# FMC_HPC_UFL_DEBUG_J1_J84.net
KiCad netlist of a schematic drawn in Altium Designer
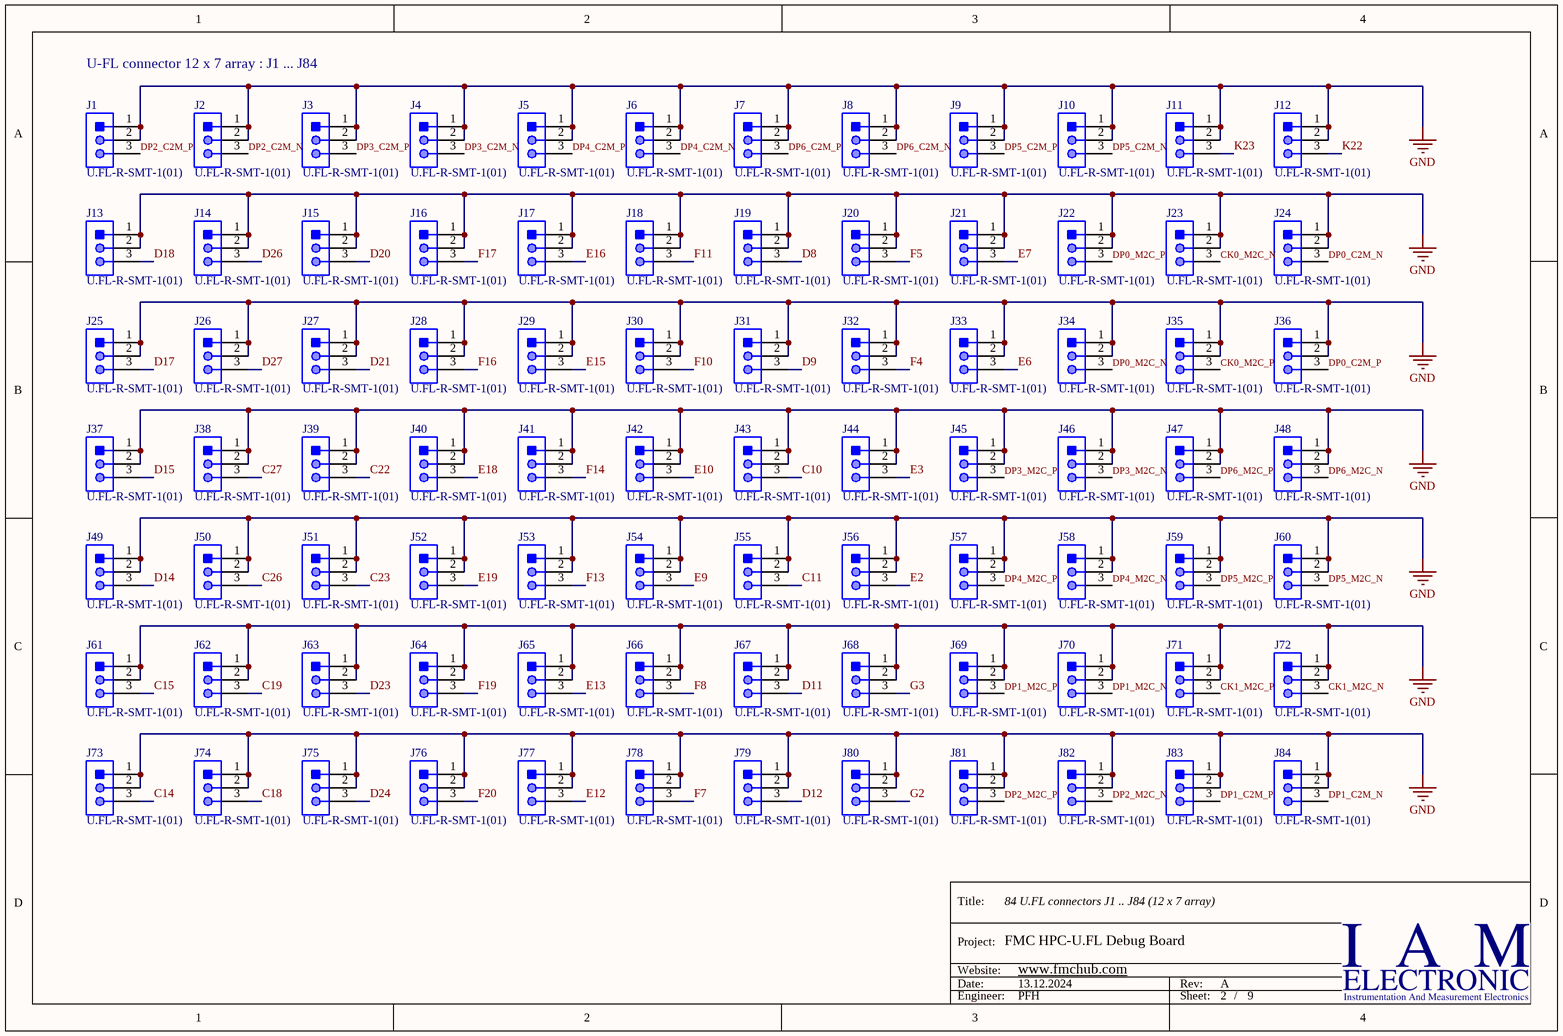
[diagram p0: FMC_HPC_UFL_DEBUG_J1_J84.SchDoc]

(export (version "E")
  (design (tool "Eeschema 10.0.6"))
  (components
    (comp (ref "J1")
      (value "U.FL-R-SMT-1(01)")
      (footprint "HRS-U.FL-R-SMT-3_V")
      (description "Ultra Small Coaxial Connector, 6 GHz, -40 to 90 degC, 3-Pin SMD, RoHS, Bulk")
      (fields (field (name "MANUFACTURER") "Hirose Electric"))
      (libsource (lib "Altium Content Vault") (part "CN-1P-M-R3"))
    )
    (comp (ref "J2")
      (value "U.FL-R-SMT-1(01)")
      (footprint "HRS-U.FL-R-SMT-3_V")
      (description "Ultra Small Coaxial Connector, 6 GHz, -40 to 90 degC, 3-Pin SMD, RoHS, Bulk")
      (fields (field (name "MANUFACTURER") "Hirose Electric"))
      (libsource (lib "Altium Content Vault") (part "CN-1P-M-R3"))
    )
    (comp (ref "J3")
      (value "U.FL-R-SMT-1(01)")
      (footprint "HRS-U.FL-R-SMT-3_V")
      (description "Ultra Small Coaxial Connector, 6 GHz, -40 to 90 degC, 3-Pin SMD, RoHS, Bulk")
      (fields (field (name "MANUFACTURER") "Hirose Electric"))
      (libsource (lib "Altium Content Vault") (part "CN-1P-M-R3"))
    )
    (comp (ref "J4")
      (value "U.FL-R-SMT-1(01)")
      (footprint "HRS-U.FL-R-SMT-3_V")
      (description "Ultra Small Coaxial Connector, 6 GHz, -40 to 90 degC, 3-Pin SMD, RoHS, Bulk")
      (fields (field (name "MANUFACTURER") "Hirose Electric"))
      (libsource (lib "Altium Content Vault") (part "CN-1P-M-R3"))
    )
    (comp (ref "J5")
      (value "U.FL-R-SMT-1(01)")
      (footprint "HRS-U.FL-R-SMT-3_V")
      (description "Ultra Small Coaxial Connector, 6 GHz, -40 to 90 degC, 3-Pin SMD, RoHS, Bulk")
      (fields (field (name "MANUFACTURER") "Hirose Electric"))
      (libsource (lib "Altium Content Vault") (part "CN-1P-M-R3"))
    )
    (comp (ref "J6")
      (value "U.FL-R-SMT-1(01)")
      (footprint "HRS-U.FL-R-SMT-3_V")
      (description "Ultra Small Coaxial Connector, 6 GHz, -40 to 90 degC, 3-Pin SMD, RoHS, Bulk")
      (fields (field (name "MANUFACTURER") "Hirose Electric"))
      (libsource (lib "Altium Content Vault") (part "CN-1P-M-R3"))
    )
    (comp (ref "J7")
      (value "U.FL-R-SMT-1(01)")
      (footprint "HRS-U.FL-R-SMT-3_V")
      (description "Ultra Small Coaxial Connector, 6 GHz, -40 to 90 degC, 3-Pin SMD, RoHS, Bulk")
      (fields (field (name "MANUFACTURER") "Hirose Electric"))
      (libsource (lib "Altium Content Vault") (part "CN-1P-M-R3"))
    )
    (comp (ref "J8")
      (value "U.FL-R-SMT-1(01)")
      (footprint "HRS-U.FL-R-SMT-3_V")
      (description "Ultra Small Coaxial Connector, 6 GHz, -40 to 90 degC, 3-Pin SMD, RoHS, Bulk")
      (fields (field (name "MANUFACTURER") "Hirose Electric"))
      (libsource (lib "Altium Content Vault") (part "CN-1P-M-R3"))
    )
    (comp (ref "J9")
      (value "U.FL-R-SMT-1(01)")
      (footprint "HRS-U.FL-R-SMT-3_V")
      (description "Ultra Small Coaxial Connector, 6 GHz, -40 to 90 degC, 3-Pin SMD, RoHS, Bulk")
      (fields (field (name "MANUFACTURER") "Hirose Electric"))
      (libsource (lib "Altium Content Vault") (part "CN-1P-M-R3"))
    )
    (comp (ref "J10")
      (value "U.FL-R-SMT-1(01)")
      (footprint "HRS-U.FL-R-SMT-3_V")
      (description "Ultra Small Coaxial Connector, 6 GHz, -40 to 90 degC, 3-Pin SMD, RoHS, Bulk")
      (fields (field (name "MANUFACTURER") "Hirose Electric"))
      (libsource (lib "Altium Content Vault") (part "CN-1P-M-R3"))
    )
    (comp (ref "J11")
      (value "U.FL-R-SMT-1(01)")
      (footprint "HRS-U.FL-R-SMT-3_V")
      (description "Ultra Small Coaxial Connector, 6 GHz, -40 to 90 degC, 3-Pin SMD, RoHS, Bulk")
      (fields (field (name "MANUFACTURER") "Hirose Electric"))
      (libsource (lib "Altium Content Vault") (part "CN-1P-M-R3"))
    )
    (comp (ref "J12")
      (value "U.FL-R-SMT-1(01)")
      (footprint "HRS-U.FL-R-SMT-3_V")
      (description "Ultra Small Coaxial Connector, 6 GHz, -40 to 90 degC, 3-Pin SMD, RoHS, Bulk")
      (fields (field (name "MANUFACTURER") "Hirose Electric"))
      (libsource (lib "Altium Content Vault") (part "CN-1P-M-R3"))
    )
    (comp (ref "J13")
      (value "U.FL-R-SMT-1(01)")
      (footprint "HRS-U.FL-R-SMT-3_V")
      (description "Ultra Small Coaxial Connector, 6 GHz, -40 to 90 degC, 3-Pin SMD, RoHS, Bulk")
      (fields (field (name "MANUFACTURER") "Hirose Electric"))
      (libsource (lib "Altium Content Vault") (part "CN-1P-M-R3"))
    )
    (comp (ref "J14")
      (value "U.FL-R-SMT-1(01)")
      (footprint "HRS-U.FL-R-SMT-3_V")
      (description "Ultra Small Coaxial Connector, 6 GHz, -40 to 90 degC, 3-Pin SMD, RoHS, Bulk")
      (fields (field (name "MANUFACTURER") "Hirose Electric"))
      (libsource (lib "Altium Content Vault") (part "CN-1P-M-R3"))
    )
    (comp (ref "J15")
      (value "U.FL-R-SMT-1(01)")
      (footprint "HRS-U.FL-R-SMT-3_V")
      (description "Ultra Small Coaxial Connector, 6 GHz, -40 to 90 degC, 3-Pin SMD, RoHS, Bulk")
      (fields (field (name "MANUFACTURER") "Hirose Electric"))
      (libsource (lib "Altium Content Vault") (part "CN-1P-M-R3"))
    )
    (comp (ref "J16")
      (value "U.FL-R-SMT-1(01)")
      (footprint "HRS-U.FL-R-SMT-3_V")
      (description "Ultra Small Coaxial Connector, 6 GHz, -40 to 90 degC, 3-Pin SMD, RoHS, Bulk")
      (fields (field (name "MANUFACTURER") "Hirose Electric"))
      (libsource (lib "Altium Content Vault") (part "CN-1P-M-R3"))
    )
    (comp (ref "J17")
      (value "U.FL-R-SMT-1(01)")
      (footprint "HRS-U.FL-R-SMT-3_V")
      (description "Ultra Small Coaxial Connector, 6 GHz, -40 to 90 degC, 3-Pin SMD, RoHS, Bulk")
      (fields (field (name "MANUFACTURER") "Hirose Electric"))
      (libsource (lib "Altium Content Vault") (part "CN-1P-M-R3"))
    )
    (comp (ref "J18")
      (value "U.FL-R-SMT-1(01)")
      (footprint "HRS-U.FL-R-SMT-3_V")
      (description "Ultra Small Coaxial Connector, 6 GHz, -40 to 90 degC, 3-Pin SMD, RoHS, Bulk")
      (fields (field (name "MANUFACTURER") "Hirose Electric"))
      (libsource (lib "Altium Content Vault") (part "CN-1P-M-R3"))
    )
    (comp (ref "J19")
      (value "U.FL-R-SMT-1(01)")
      (footprint "HRS-U.FL-R-SMT-3_V")
      (description "Ultra Small Coaxial Connector, 6 GHz, -40 to 90 degC, 3-Pin SMD, RoHS, Bulk")
      (fields (field (name "MANUFACTURER") "Hirose Electric"))
      (libsource (lib "Altium Content Vault") (part "CN-1P-M-R3"))
    )
    (comp (ref "J20")
      (value "U.FL-R-SMT-1(01)")
      (footprint "HRS-U.FL-R-SMT-3_V")
      (description "Ultra Small Coaxial Connector, 6 GHz, -40 to 90 degC, 3-Pin SMD, RoHS, Bulk")
      (fields (field (name "MANUFACTURER") "Hirose Electric"))
      (libsource (lib "Altium Content Vault") (part "CN-1P-M-R3"))
    )
    (comp (ref "J21")
      (value "U.FL-R-SMT-1(01)")
      (footprint "HRS-U.FL-R-SMT-3_V")
      (description "Ultra Small Coaxial Connector, 6 GHz, -40 to 90 degC, 3-Pin SMD, RoHS, Bulk")
      (fields (field (name "MANUFACTURER") "Hirose Electric"))
      (libsource (lib "Altium Content Vault") (part "CN-1P-M-R3"))
    )
    (comp (ref "J22")
      (value "U.FL-R-SMT-1(01)")
      (footprint "HRS-U.FL-R-SMT-3_V")
      (description "Ultra Small Coaxial Connector, 6 GHz, -40 to 90 degC, 3-Pin SMD, RoHS, Bulk")
      (fields (field (name "MANUFACTURER") "Hirose Electric"))
      (libsource (lib "Altium Content Vault") (part "CN-1P-M-R3"))
    )
    (comp (ref "J23")
      (value "U.FL-R-SMT-1(01)")
      (footprint "HRS-U.FL-R-SMT-3_V")
      (description "Ultra Small Coaxial Connector, 6 GHz, -40 to 90 degC, 3-Pin SMD, RoHS, Bulk")
      (fields (field (name "MANUFACTURER") "Hirose Electric"))
      (libsource (lib "Altium Content Vault") (part "CN-1P-M-R3"))
    )
    (comp (ref "J24")
      (value "U.FL-R-SMT-1(01)")
      (footprint "HRS-U.FL-R-SMT-3_V")
      (description "Ultra Small Coaxial Connector, 6 GHz, -40 to 90 degC, 3-Pin SMD, RoHS, Bulk")
      (fields (field (name "MANUFACTURER") "Hirose Electric"))
      (libsource (lib "Altium Content Vault") (part "CN-1P-M-R3"))
    )
    (comp (ref "J25")
      (value "U.FL-R-SMT-1(01)")
      (footprint "HRS-U.FL-R-SMT-3_V")
      (description "Ultra Small Coaxial Connector, 6 GHz, -40 to 90 degC, 3-Pin SMD, RoHS, Bulk")
      (fields (field (name "MANUFACTURER") "Hirose Electric"))
      (libsource (lib "Altium Content Vault") (part "CN-1P-M-R3"))
    )
    (comp (ref "J26")
      (value "U.FL-R-SMT-1(01)")
      (footprint "HRS-U.FL-R-SMT-3_V")
      (description "Ultra Small Coaxial Connector, 6 GHz, -40 to 90 degC, 3-Pin SMD, RoHS, Bulk")
      (fields (field (name "MANUFACTURER") "Hirose Electric"))
      (libsource (lib "Altium Content Vault") (part "CN-1P-M-R3"))
    )
    (comp (ref "J27")
      (value "U.FL-R-SMT-1(01)")
      (footprint "HRS-U.FL-R-SMT-3_V")
      (description "Ultra Small Coaxial Connector, 6 GHz, -40 to 90 degC, 3-Pin SMD, RoHS, Bulk")
      (fields (field (name "MANUFACTURER") "Hirose Electric"))
      (libsource (lib "Altium Content Vault") (part "CN-1P-M-R3"))
    )
    (comp (ref "J28")
      (value "U.FL-R-SMT-1(01)")
      (footprint "HRS-U.FL-R-SMT-3_V")
      (description "Ultra Small Coaxial Connector, 6 GHz, -40 to 90 degC, 3-Pin SMD, RoHS, Bulk")
      (fields (field (name "MANUFACTURER") "Hirose Electric"))
      (libsource (lib "Altium Content Vault") (part "CN-1P-M-R3"))
    )
    (comp (ref "J29")
      (value "U.FL-R-SMT-1(01)")
      (footprint "HRS-U.FL-R-SMT-3_V")
      (description "Ultra Small Coaxial Connector, 6 GHz, -40 to 90 degC, 3-Pin SMD, RoHS, Bulk")
      (fields (field (name "MANUFACTURER") "Hirose Electric"))
      (libsource (lib "Altium Content Vault") (part "CN-1P-M-R3"))
    )
    (comp (ref "J30")
      (value "U.FL-R-SMT-1(01)")
      (footprint "HRS-U.FL-R-SMT-3_V")
      (description "Ultra Small Coaxial Connector, 6 GHz, -40 to 90 degC, 3-Pin SMD, RoHS, Bulk")
      (fields (field (name "MANUFACTURER") "Hirose Electric"))
      (libsource (lib "Altium Content Vault") (part "CN-1P-M-R3"))
    )
    (comp (ref "J31")
      (value "U.FL-R-SMT-1(01)")
      (footprint "HRS-U.FL-R-SMT-3_V")
      (description "Ultra Small Coaxial Connector, 6 GHz, -40 to 90 degC, 3-Pin SMD, RoHS, Bulk")
      (fields (field (name "MANUFACTURER") "Hirose Electric"))
      (libsource (lib "Altium Content Vault") (part "CN-1P-M-R3"))
    )
    (comp (ref "J32")
      (value "U.FL-R-SMT-1(01)")
      (footprint "HRS-U.FL-R-SMT-3_V")
      (description "Ultra Small Coaxial Connector, 6 GHz, -40 to 90 degC, 3-Pin SMD, RoHS, Bulk")
      (fields (field (name "MANUFACTURER") "Hirose Electric"))
      (libsource (lib "Altium Content Vault") (part "CN-1P-M-R3"))
    )
    (comp (ref "J33")
      (value "U.FL-R-SMT-1(01)")
      (footprint "HRS-U.FL-R-SMT-3_V")
      (description "Ultra Small Coaxial Connector, 6 GHz, -40 to 90 degC, 3-Pin SMD, RoHS, Bulk")
      (fields (field (name "MANUFACTURER") "Hirose Electric"))
      (libsource (lib "Altium Content Vault") (part "CN-1P-M-R3"))
    )
    (comp (ref "J34")
      (value "U.FL-R-SMT-1(01)")
      (footprint "HRS-U.FL-R-SMT-3_V")
      (description "Ultra Small Coaxial Connector, 6 GHz, -40 to 90 degC, 3-Pin SMD, RoHS, Bulk")
      (fields (field (name "MANUFACTURER") "Hirose Electric"))
      (libsource (lib "Altium Content Vault") (part "CN-1P-M-R3"))
    )
    (comp (ref "J35")
      (value "U.FL-R-SMT-1(01)")
      (footprint "HRS-U.FL-R-SMT-3_V")
      (description "Ultra Small Coaxial Connector, 6 GHz, -40 to 90 degC, 3-Pin SMD, RoHS, Bulk")
      (fields (field (name "MANUFACTURER") "Hirose Electric"))
      (libsource (lib "Altium Content Vault") (part "CN-1P-M-R3"))
    )
    (comp (ref "J36")
      (value "U.FL-R-SMT-1(01)")
      (footprint "HRS-U.FL-R-SMT-3_V")
      (description "Ultra Small Coaxial Connector, 6 GHz, -40 to 90 degC, 3-Pin SMD, RoHS, Bulk")
      (fields (field (name "MANUFACTURER") "Hirose Electric"))
      (libsource (lib "Altium Content Vault") (part "CN-1P-M-R3"))
    )
    (comp (ref "J37")
      (value "U.FL-R-SMT-1(01)")
      (footprint "HRS-U.FL-R-SMT-3_V")
      (description "Ultra Small Coaxial Connector, 6 GHz, -40 to 90 degC, 3-Pin SMD, RoHS, Bulk")
      (fields (field (name "MANUFACTURER") "Hirose Electric"))
      (libsource (lib "Altium Content Vault") (part "CN-1P-M-R3"))
    )
    (comp (ref "J38")
      (value "U.FL-R-SMT-1(01)")
      (footprint "HRS-U.FL-R-SMT-3_V")
      (description "Ultra Small Coaxial Connector, 6 GHz, -40 to 90 degC, 3-Pin SMD, RoHS, Bulk")
      (fields (field (name "MANUFACTURER") "Hirose Electric"))
      (libsource (lib "Altium Content Vault") (part "CN-1P-M-R3"))
    )
    (comp (ref "J39")
      (value "U.FL-R-SMT-1(01)")
      (footprint "HRS-U.FL-R-SMT-3_V")
      (description "Ultra Small Coaxial Connector, 6 GHz, -40 to 90 degC, 3-Pin SMD, RoHS, Bulk")
      (fields (field (name "MANUFACTURER") "Hirose Electric"))
      (libsource (lib "Altium Content Vault") (part "CN-1P-M-R3"))
    )
    (comp (ref "J40")
      (value "U.FL-R-SMT-1(01)")
      (footprint "HRS-U.FL-R-SMT-3_V")
      (description "Ultra Small Coaxial Connector, 6 GHz, -40 to 90 degC, 3-Pin SMD, RoHS, Bulk")
      (fields (field (name "MANUFACTURER") "Hirose Electric"))
      (libsource (lib "Altium Content Vault") (part "CN-1P-M-R3"))
    )
    (comp (ref "J41")
      (value "U.FL-R-SMT-1(01)")
      (footprint "HRS-U.FL-R-SMT-3_V")
      (description "Ultra Small Coaxial Connector, 6 GHz, -40 to 90 degC, 3-Pin SMD, RoHS, Bulk")
      (fields (field (name "MANUFACTURER") "Hirose Electric"))
      (libsource (lib "Altium Content Vault") (part "CN-1P-M-R3"))
    )
    (comp (ref "J42")
      (value "U.FL-R-SMT-1(01)")
      (footprint "HRS-U.FL-R-SMT-3_V")
      (description "Ultra Small Coaxial Connector, 6 GHz, -40 to 90 degC, 3-Pin SMD, RoHS, Bulk")
      (fields (field (name "MANUFACTURER") "Hirose Electric"))
      (libsource (lib "Altium Content Vault") (part "CN-1P-M-R3"))
    )
    (comp (ref "J43")
      (value "U.FL-R-SMT-1(01)")
      (footprint "HRS-U.FL-R-SMT-3_V")
      (description "Ultra Small Coaxial Connector, 6 GHz, -40 to 90 degC, 3-Pin SMD, RoHS, Bulk")
      (fields (field (name "MANUFACTURER") "Hirose Electric"))
      (libsource (lib "Altium Content Vault") (part "CN-1P-M-R3"))
    )
    (comp (ref "J44")
      (value "U.FL-R-SMT-1(01)")
      (footprint "HRS-U.FL-R-SMT-3_V")
      (description "Ultra Small Coaxial Connector, 6 GHz, -40 to 90 degC, 3-Pin SMD, RoHS, Bulk")
      (fields (field (name "MANUFACTURER") "Hirose Electric"))
      (libsource (lib "Altium Content Vault") (part "CN-1P-M-R3"))
    )
    (comp (ref "J45")
      (value "U.FL-R-SMT-1(01)")
      (footprint "HRS-U.FL-R-SMT-3_V")
      (description "Ultra Small Coaxial Connector, 6 GHz, -40 to 90 degC, 3-Pin SMD, RoHS, Bulk")
      (fields (field (name "MANUFACTURER") "Hirose Electric"))
      (libsource (lib "Altium Content Vault") (part "CN-1P-M-R3"))
    )
    (comp (ref "J46")
      (value "U.FL-R-SMT-1(01)")
      (footprint "HRS-U.FL-R-SMT-3_V")
      (description "Ultra Small Coaxial Connector, 6 GHz, -40 to 90 degC, 3-Pin SMD, RoHS, Bulk")
      (fields (field (name "MANUFACTURER") "Hirose Electric"))
      (libsource (lib "Altium Content Vault") (part "CN-1P-M-R3"))
    )
    (comp (ref "J47")
      (value "U.FL-R-SMT-1(01)")
      (footprint "HRS-U.FL-R-SMT-3_V")
      (description "Ultra Small Coaxial Connector, 6 GHz, -40 to 90 degC, 3-Pin SMD, RoHS, Bulk")
      (fields (field (name "MANUFACTURER") "Hirose Electric"))
      (libsource (lib "Altium Content Vault") (part "CN-1P-M-R3"))
    )
    (comp (ref "J48")
      (value "U.FL-R-SMT-1(01)")
      (footprint "HRS-U.FL-R-SMT-3_V")
      (description "Ultra Small Coaxial Connector, 6 GHz, -40 to 90 degC, 3-Pin SMD, RoHS, Bulk")
      (fields (field (name "MANUFACTURER") "Hirose Electric"))
      (libsource (lib "Altium Content Vault") (part "CN-1P-M-R3"))
    )
    (comp (ref "J49")
      (value "U.FL-R-SMT-1(01)")
      (footprint "HRS-U.FL-R-SMT-3_V")
      (description "Ultra Small Coaxial Connector, 6 GHz, -40 to 90 degC, 3-Pin SMD, RoHS, Bulk")
      (fields (field (name "MANUFACTURER") "Hirose Electric"))
      (libsource (lib "Altium Content Vault") (part "CN-1P-M-R3"))
    )
    (comp (ref "J50")
      (value "U.FL-R-SMT-1(01)")
      (footprint "HRS-U.FL-R-SMT-3_V")
      (description "Ultra Small Coaxial Connector, 6 GHz, -40 to 90 degC, 3-Pin SMD, RoHS, Bulk")
      (fields (field (name "MANUFACTURER") "Hirose Electric"))
      (libsource (lib "Altium Content Vault") (part "CN-1P-M-R3"))
    )
    (comp (ref "J51")
      (value "U.FL-R-SMT-1(01)")
      (footprint "HRS-U.FL-R-SMT-3_V")
      (description "Ultra Small Coaxial Connector, 6 GHz, -40 to 90 degC, 3-Pin SMD, RoHS, Bulk")
      (fields (field (name "MANUFACTURER") "Hirose Electric"))
      (libsource (lib "Altium Content Vault") (part "CN-1P-M-R3"))
    )
    (comp (ref "J52")
      (value "U.FL-R-SMT-1(01)")
      (footprint "HRS-U.FL-R-SMT-3_V")
      (description "Ultra Small Coaxial Connector, 6 GHz, -40 to 90 degC, 3-Pin SMD, RoHS, Bulk")
      (fields (field (name "MANUFACTURER") "Hirose Electric"))
      (libsource (lib "Altium Content Vault") (part "CN-1P-M-R3"))
    )
    (comp (ref "J53")
      (value "U.FL-R-SMT-1(01)")
      (footprint "HRS-U.FL-R-SMT-3_V")
      (description "Ultra Small Coaxial Connector, 6 GHz, -40 to 90 degC, 3-Pin SMD, RoHS, Bulk")
      (fields (field (name "MANUFACTURER") "Hirose Electric"))
      (libsource (lib "Altium Content Vault") (part "CN-1P-M-R3"))
    )
    (comp (ref "J54")
      (value "U.FL-R-SMT-1(01)")
      (footprint "HRS-U.FL-R-SMT-3_V")
      (description "Ultra Small Coaxial Connector, 6 GHz, -40 to 90 degC, 3-Pin SMD, RoHS, Bulk")
      (fields (field (name "MANUFACTURER") "Hirose Electric"))
      (libsource (lib "Altium Content Vault") (part "CN-1P-M-R3"))
    )
    (comp (ref "J55")
      (value "U.FL-R-SMT-1(01)")
      (footprint "HRS-U.FL-R-SMT-3_V")
      (description "Ultra Small Coaxial Connector, 6 GHz, -40 to 90 degC, 3-Pin SMD, RoHS, Bulk")
      (fields (field (name "MANUFACTURER") "Hirose Electric"))
      (libsource (lib "Altium Content Vault") (part "CN-1P-M-R3"))
    )
    (comp (ref "J56")
      (value "U.FL-R-SMT-1(01)")
      (footprint "HRS-U.FL-R-SMT-3_V")
      (description "Ultra Small Coaxial Connector, 6 GHz, -40 to 90 degC, 3-Pin SMD, RoHS, Bulk")
      (fields (field (name "MANUFACTURER") "Hirose Electric"))
      (libsource (lib "Altium Content Vault") (part "CN-1P-M-R3"))
    )
    (comp (ref "J57")
      (value "U.FL-R-SMT-1(01)")
      (footprint "HRS-U.FL-R-SMT-3_V")
      (description "Ultra Small Coaxial Connector, 6 GHz, -40 to 90 degC, 3-Pin SMD, RoHS, Bulk")
      (fields (field (name "MANUFACTURER") "Hirose Electric"))
      (libsource (lib "Altium Content Vault") (part "CN-1P-M-R3"))
    )
    (comp (ref "J58")
      (value "U.FL-R-SMT-1(01)")
      (footprint "HRS-U.FL-R-SMT-3_V")
      (description "Ultra Small Coaxial Connector, 6 GHz, -40 to 90 degC, 3-Pin SMD, RoHS, Bulk")
      (fields (field (name "MANUFACTURER") "Hirose Electric"))
      (libsource (lib "Altium Content Vault") (part "CN-1P-M-R3"))
    )
    (comp (ref "J59")
      (value "U.FL-R-SMT-1(01)")
      (footprint "HRS-U.FL-R-SMT-3_V")
      (description "Ultra Small Coaxial Connector, 6 GHz, -40 to 90 degC, 3-Pin SMD, RoHS, Bulk")
      (fields (field (name "MANUFACTURER") "Hirose Electric"))
      (libsource (lib "Altium Content Vault") (part "CN-1P-M-R3"))
    )
    (comp (ref "J60")
      (value "U.FL-R-SMT-1(01)")
      (footprint "HRS-U.FL-R-SMT-3_V")
      (description "Ultra Small Coaxial Connector, 6 GHz, -40 to 90 degC, 3-Pin SMD, RoHS, Bulk")
      (fields (field (name "MANUFACTURER") "Hirose Electric"))
      (libsource (lib "Altium Content Vault") (part "CN-1P-M-R3"))
    )
    (comp (ref "J61")
      (value "U.FL-R-SMT-1(01)")
      (footprint "HRS-U.FL-R-SMT-3_V")
      (description "Ultra Small Coaxial Connector, 6 GHz, -40 to 90 degC, 3-Pin SMD, RoHS, Bulk")
      (fields (field (name "MANUFACTURER") "Hirose Electric"))
      (libsource (lib "Altium Content Vault") (part "CN-1P-M-R3"))
    )
    (comp (ref "J62")
      (value "U.FL-R-SMT-1(01)")
      (footprint "HRS-U.FL-R-SMT-3_V")
      (description "Ultra Small Coaxial Connector, 6 GHz, -40 to 90 degC, 3-Pin SMD, RoHS, Bulk")
      (fields (field (name "MANUFACTURER") "Hirose Electric"))
      (libsource (lib "Altium Content Vault") (part "CN-1P-M-R3"))
    )
    (comp (ref "J63")
      (value "U.FL-R-SMT-1(01)")
      (footprint "HRS-U.FL-R-SMT-3_V")
      (description "Ultra Small Coaxial Connector, 6 GHz, -40 to 90 degC, 3-Pin SMD, RoHS, Bulk")
      (fields (field (name "MANUFACTURER") "Hirose Electric"))
      (libsource (lib "Altium Content Vault") (part "CN-1P-M-R3"))
    )
    (comp (ref "J64")
      (value "U.FL-R-SMT-1(01)")
      (footprint "HRS-U.FL-R-SMT-3_V")
      (description "Ultra Small Coaxial Connector, 6 GHz, -40 to 90 degC, 3-Pin SMD, RoHS, Bulk")
      (fields (field (name "MANUFACTURER") "Hirose Electric"))
      (libsource (lib "Altium Content Vault") (part "CN-1P-M-R3"))
    )
    (comp (ref "J65")
      (value "U.FL-R-SMT-1(01)")
      (footprint "HRS-U.FL-R-SMT-3_V")
      (description "Ultra Small Coaxial Connector, 6 GHz, -40 to 90 degC, 3-Pin SMD, RoHS, Bulk")
      (fields (field (name "MANUFACTURER") "Hirose Electric"))
      (libsource (lib "Altium Content Vault") (part "CN-1P-M-R3"))
    )
    (comp (ref "J66")
      (value "U.FL-R-SMT-1(01)")
      (footprint "HRS-U.FL-R-SMT-3_V")
      (description "Ultra Small Coaxial Connector, 6 GHz, -40 to 90 degC, 3-Pin SMD, RoHS, Bulk")
      (fields (field (name "MANUFACTURER") "Hirose Electric"))
      (libsource (lib "Altium Content Vault") (part "CN-1P-M-R3"))
    )
    (comp (ref "J67")
      (value "U.FL-R-SMT-1(01)")
      (footprint "HRS-U.FL-R-SMT-3_V")
      (description "Ultra Small Coaxial Connector, 6 GHz, -40 to 90 degC, 3-Pin SMD, RoHS, Bulk")
      (fields (field (name "MANUFACTURER") "Hirose Electric"))
      (libsource (lib "Altium Content Vault") (part "CN-1P-M-R3"))
    )
    (comp (ref "J68")
      (value "U.FL-R-SMT-1(01)")
      (footprint "HRS-U.FL-R-SMT-3_V")
      (description "Ultra Small Coaxial Connector, 6 GHz, -40 to 90 degC, 3-Pin SMD, RoHS, Bulk")
      (fields (field (name "MANUFACTURER") "Hirose Electric"))
      (libsource (lib "Altium Content Vault") (part "CN-1P-M-R3"))
    )
    (comp (ref "J69")
      (value "U.FL-R-SMT-1(01)")
      (footprint "HRS-U.FL-R-SMT-3_V")
      (description "Ultra Small Coaxial Connector, 6 GHz, -40 to 90 degC, 3-Pin SMD, RoHS, Bulk")
      (fields (field (name "MANUFACTURER") "Hirose Electric"))
      (libsource (lib "Altium Content Vault") (part "CN-1P-M-R3"))
    )
    (comp (ref "J70")
      (value "U.FL-R-SMT-1(01)")
      (footprint "HRS-U.FL-R-SMT-3_V")
      (description "Ultra Small Coaxial Connector, 6 GHz, -40 to 90 degC, 3-Pin SMD, RoHS, Bulk")
      (fields (field (name "MANUFACTURER") "Hirose Electric"))
      (libsource (lib "Altium Content Vault") (part "CN-1P-M-R3"))
    )
    (comp (ref "J71")
      (value "U.FL-R-SMT-1(01)")
      (footprint "HRS-U.FL-R-SMT-3_V")
      (description "Ultra Small Coaxial Connector, 6 GHz, -40 to 90 degC, 3-Pin SMD, RoHS, Bulk")
      (fields (field (name "MANUFACTURER") "Hirose Electric"))
      (libsource (lib "Altium Content Vault") (part "CN-1P-M-R3"))
    )
    (comp (ref "J72")
      (value "U.FL-R-SMT-1(01)")
      (footprint "HRS-U.FL-R-SMT-3_V")
      (description "Ultra Small Coaxial Connector, 6 GHz, -40 to 90 degC, 3-Pin SMD, RoHS, Bulk")
      (fields (field (name "MANUFACTURER") "Hirose Electric"))
      (libsource (lib "Altium Content Vault") (part "CN-1P-M-R3"))
    )
    (comp (ref "J73")
      (value "U.FL-R-SMT-1(01)")
      (footprint "HRS-U.FL-R-SMT-3_V")
      (description "Ultra Small Coaxial Connector, 6 GHz, -40 to 90 degC, 3-Pin SMD, RoHS, Bulk")
      (fields (field (name "MANUFACTURER") "Hirose Electric"))
      (libsource (lib "Altium Content Vault") (part "CN-1P-M-R3"))
    )
    (comp (ref "J74")
      (value "U.FL-R-SMT-1(01)")
      (footprint "HRS-U.FL-R-SMT-3_V")
      (description "Ultra Small Coaxial Connector, 6 GHz, -40 to 90 degC, 3-Pin SMD, RoHS, Bulk")
      (fields (field (name "MANUFACTURER") "Hirose Electric"))
      (libsource (lib "Altium Content Vault") (part "CN-1P-M-R3"))
    )
    (comp (ref "J75")
      (value "U.FL-R-SMT-1(01)")
      (footprint "HRS-U.FL-R-SMT-3_V")
      (description "Ultra Small Coaxial Connector, 6 GHz, -40 to 90 degC, 3-Pin SMD, RoHS, Bulk")
      (fields (field (name "MANUFACTURER") "Hirose Electric"))
      (libsource (lib "Altium Content Vault") (part "CN-1P-M-R3"))
    )
    (comp (ref "J76")
      (value "U.FL-R-SMT-1(01)")
      (footprint "HRS-U.FL-R-SMT-3_V")
      (description "Ultra Small Coaxial Connector, 6 GHz, -40 to 90 degC, 3-Pin SMD, RoHS, Bulk")
      (fields (field (name "MANUFACTURER") "Hirose Electric"))
      (libsource (lib "Altium Content Vault") (part "CN-1P-M-R3"))
    )
    (comp (ref "J77")
      (value "U.FL-R-SMT-1(01)")
      (footprint "HRS-U.FL-R-SMT-3_V")
      (description "Ultra Small Coaxial Connector, 6 GHz, -40 to 90 degC, 3-Pin SMD, RoHS, Bulk")
      (fields (field (name "MANUFACTURER") "Hirose Electric"))
      (libsource (lib "Altium Content Vault") (part "CN-1P-M-R3"))
    )
    (comp (ref "J78")
      (value "U.FL-R-SMT-1(01)")
      (footprint "HRS-U.FL-R-SMT-3_V")
      (description "Ultra Small Coaxial Connector, 6 GHz, -40 to 90 degC, 3-Pin SMD, RoHS, Bulk")
      (fields (field (name "MANUFACTURER") "Hirose Electric"))
      (libsource (lib "Altium Content Vault") (part "CN-1P-M-R3"))
    )
    (comp (ref "J79")
      (value "U.FL-R-SMT-1(01)")
      (footprint "HRS-U.FL-R-SMT-3_V")
      (description "Ultra Small Coaxial Connector, 6 GHz, -40 to 90 degC, 3-Pin SMD, RoHS, Bulk")
      (fields (field (name "MANUFACTURER") "Hirose Electric"))
      (libsource (lib "Altium Content Vault") (part "CN-1P-M-R3"))
    )
    (comp (ref "J80")
      (value "U.FL-R-SMT-1(01)")
      (footprint "HRS-U.FL-R-SMT-3_V")
      (description "Ultra Small Coaxial Connector, 6 GHz, -40 to 90 degC, 3-Pin SMD, RoHS, Bulk")
      (fields (field (name "MANUFACTURER") "Hirose Electric"))
      (libsource (lib "Altium Content Vault") (part "CN-1P-M-R3"))
    )
    (comp (ref "J81")
      (value "U.FL-R-SMT-1(01)")
      (footprint "HRS-U.FL-R-SMT-3_V")
      (description "Ultra Small Coaxial Connector, 6 GHz, -40 to 90 degC, 3-Pin SMD, RoHS, Bulk")
      (fields (field (name "MANUFACTURER") "Hirose Electric"))
      (libsource (lib "Altium Content Vault") (part "CN-1P-M-R3"))
    )
    (comp (ref "J82")
      (value "U.FL-R-SMT-1(01)")
      (footprint "HRS-U.FL-R-SMT-3_V")
      (description "Ultra Small Coaxial Connector, 6 GHz, -40 to 90 degC, 3-Pin SMD, RoHS, Bulk")
      (fields (field (name "MANUFACTURER") "Hirose Electric"))
      (libsource (lib "Altium Content Vault") (part "CN-1P-M-R3"))
    )
    (comp (ref "J83")
      (value "U.FL-R-SMT-1(01)")
      (footprint "HRS-U.FL-R-SMT-3_V")
      (description "Ultra Small Coaxial Connector, 6 GHz, -40 to 90 degC, 3-Pin SMD, RoHS, Bulk")
      (fields (field (name "MANUFACTURER") "Hirose Electric"))
      (libsource (lib "Altium Content Vault") (part "CN-1P-M-R3"))
    )
    (comp (ref "J84")
      (value "U.FL-R-SMT-1(01)")
      (footprint "HRS-U.FL-R-SMT-3_V")
      (description "Ultra Small Coaxial Connector, 6 GHz, -40 to 90 degC, 3-Pin SMD, RoHS, Bulk")
      (fields (field (name "MANUFACTURER") "Hirose Electric"))
      (libsource (lib "Altium Content Vault") (part "CN-1P-M-R3"))
    )
  )
  (nets
    (net (code "1") (name "/C10") (class "Default")
      (node (ref "J43") (pin "3") (pinfunction "3_3") (pintype "passive"))
    )
    (net (code "2") (name "/C11") (class "Default")
      (node (ref "J55") (pin "3") (pinfunction "3_3") (pintype "passive"))
    )
    (net (code "3") (name "/C14") (class "Default")
      (node (ref "J73") (pin "3") (pinfunction "3_3") (pintype "passive"))
    )
    (net (code "4") (name "/C15") (class "Default")
      (node (ref "J61") (pin "3") (pinfunction "3_3") (pintype "passive"))
    )
    (net (code "5") (name "/C18") (class "Default")
      (node (ref "J74") (pin "3") (pinfunction "3_3") (pintype "passive"))
    )
    (net (code "6") (name "/C19") (class "Default")
      (node (ref "J62") (pin "3") (pinfunction "3_3") (pintype "passive"))
    )
    (net (code "7") (name "/C22") (class "Default")
      (node (ref "J39") (pin "3") (pinfunction "3_3") (pintype "passive"))
    )
    (net (code "8") (name "/C23") (class "Default")
      (node (ref "J51") (pin "3") (pinfunction "3_3") (pintype "passive"))
    )
    (net (code "9") (name "/C26") (class "Default")
      (node (ref "J50") (pin "3") (pinfunction "3_3") (pintype "passive"))
    )
    (net (code "10") (name "/C27") (class "Default")
      (node (ref "J38") (pin "3") (pinfunction "3_3") (pintype "passive"))
    )
    (net (code "11") (name "/CK0_M2C_N") (class "Default")
      (node (ref "J23") (pin "3") (pinfunction "3_3") (pintype "passive"))
    )
    (net (code "12") (name "/CK0_M2C_P") (class "Default")
      (node (ref "J35") (pin "3") (pinfunction "3_3") (pintype "passive"))
    )
    (net (code "13") (name "/CK1_M2C_N") (class "Default")
      (node (ref "J72") (pin "3") (pinfunction "3_3") (pintype "passive"))
    )
    (net (code "14") (name "/CK1_M2C_P") (class "Default")
      (node (ref "J71") (pin "3") (pinfunction "3_3") (pintype "passive"))
    )
    (net (code "15") (name "/D8") (class "Default")
      (node (ref "J19") (pin "3") (pinfunction "3_3") (pintype "passive"))
    )
    (net (code "16") (name "/D9") (class "Default")
      (node (ref "J31") (pin "3") (pinfunction "3_3") (pintype "passive"))
    )
    (net (code "17") (name "/D11") (class "Default")
      (node (ref "J67") (pin "3") (pinfunction "3_3") (pintype "passive"))
    )
    (net (code "18") (name "/D12") (class "Default")
      (node (ref "J79") (pin "3") (pinfunction "3_3") (pintype "passive"))
    )
    (net (code "19") (name "/D14") (class "Default")
      (node (ref "J49") (pin "3") (pinfunction "3_3") (pintype "passive"))
    )
    (net (code "20") (name "/D15") (class "Default")
      (node (ref "J37") (pin "3") (pinfunction "3_3") (pintype "passive"))
    )
    (net (code "21") (name "/D17") (class "Default")
      (node (ref "J25") (pin "3") (pinfunction "3_3") (pintype "passive"))
    )
    (net (code "22") (name "/D18") (class "Default")
      (node (ref "J13") (pin "3") (pinfunction "3_3") (pintype "passive"))
    )
    (net (code "23") (name "/D20") (class "Default")
      (node (ref "J15") (pin "3") (pinfunction "3_3") (pintype "passive"))
    )
    (net (code "24") (name "/D21") (class "Default")
      (node (ref "J27") (pin "3") (pinfunction "3_3") (pintype "passive"))
    )
    (net (code "25") (name "/D23") (class "Default")
      (node (ref "J63") (pin "3") (pinfunction "3_3") (pintype "passive"))
    )
    (net (code "26") (name "/D24") (class "Default")
      (node (ref "J75") (pin "3") (pinfunction "3_3") (pintype "passive"))
    )
    (net (code "27") (name "/D26") (class "Default")
      (node (ref "J14") (pin "3") (pinfunction "3_3") (pintype "passive"))
    )
    (net (code "28") (name "/D27") (class "Default")
      (node (ref "J26") (pin "3") (pinfunction "3_3") (pintype "passive"))
    )
    (net (code "29") (name "/DP0_C2M_N") (class "Default")
      (node (ref "J24") (pin "3") (pinfunction "3_3") (pintype "passive"))
    )
    (net (code "30") (name "/DP0_C2M_P") (class "Default")
      (node (ref "J36") (pin "3") (pinfunction "3_3") (pintype "passive"))
    )
    (net (code "31") (name "/DP0_M2C_N") (class "Default")
      (node (ref "J34") (pin "3") (pinfunction "3_3") (pintype "passive"))
    )
    (net (code "32") (name "/DP0_M2C_P") (class "Default")
      (node (ref "J22") (pin "3") (pinfunction "3_3") (pintype "passive"))
    )
    (net (code "33") (name "/DP1_C2M_N") (class "Default")
      (node (ref "J84") (pin "3") (pinfunction "3_3") (pintype "passive"))
    )
    (net (code "34") (name "/DP1_C2M_P") (class "Default")
      (node (ref "J83") (pin "3") (pinfunction "3_3") (pintype "passive"))
    )
    (net (code "35") (name "/DP1_M2C_N") (class "Default")
      (node (ref "J70") (pin "3") (pinfunction "3_3") (pintype "passive"))
    )
    (net (code "36") (name "/DP1_M2C_P") (class "Default")
      (node (ref "J69") (pin "3") (pinfunction "3_3") (pintype "passive"))
    )
    (net (code "37") (name "/DP2_C2M_N") (class "Default")
      (node (ref "J2") (pin "3") (pinfunction "3_3") (pintype "passive"))
    )
    (net (code "38") (name "/DP2_C2M_P") (class "Default")
      (node (ref "J1") (pin "3") (pinfunction "3_3") (pintype "passive"))
    )
    (net (code "39") (name "/DP2_M2C_N") (class "Default")
      (node (ref "J82") (pin "3") (pinfunction "3_3") (pintype "passive"))
    )
    (net (code "40") (name "/DP2_M2C_P") (class "Default")
      (node (ref "J81") (pin "3") (pinfunction "3_3") (pintype "passive"))
    )
    (net (code "41") (name "/DP3_C2M_N") (class "Default")
      (node (ref "J4") (pin "3") (pinfunction "3_3") (pintype "passive"))
    )
    (net (code "42") (name "/DP3_C2M_P") (class "Default")
      (node (ref "J3") (pin "3") (pinfunction "3_3") (pintype "passive"))
    )
    (net (code "43") (name "/DP3_M2C_N") (class "Default")
      (node (ref "J46") (pin "3") (pinfunction "3_3") (pintype "passive"))
    )
    (net (code "44") (name "/DP3_M2C_P") (class "Default")
      (node (ref "J45") (pin "3") (pinfunction "3_3") (pintype "passive"))
    )
    (net (code "45") (name "/DP4_C2M_N") (class "Default")
      (node (ref "J6") (pin "3") (pinfunction "3_3") (pintype "passive"))
    )
    (net (code "46") (name "/DP4_C2M_P") (class "Default")
      (node (ref "J5") (pin "3") (pinfunction "3_3") (pintype "passive"))
    )
    (net (code "47") (name "/DP4_M2C_N") (class "Default")
      (node (ref "J58") (pin "3") (pinfunction "3_3") (pintype "passive"))
    )
    (net (code "48") (name "/DP4_M2C_P") (class "Default")
      (node (ref "J57") (pin "3") (pinfunction "3_3") (pintype "passive"))
    )
    (net (code "49") (name "/DP5_C2M_N") (class "Default")
      (node (ref "J10") (pin "3") (pinfunction "3_3") (pintype "passive"))
    )
    (net (code "50") (name "/DP5_C2M_P") (class "Default")
      (node (ref "J9") (pin "3") (pinfunction "3_3") (pintype "passive"))
    )
    (net (code "51") (name "/DP5_M2C_N") (class "Default")
      (node (ref "J60") (pin "3") (pinfunction "3_3") (pintype "passive"))
    )
    (net (code "52") (name "/DP5_M2C_P") (class "Default")
      (node (ref "J59") (pin "3") (pinfunction "3_3") (pintype "passive"))
    )
    (net (code "53") (name "/DP6_C2M_N") (class "Default")
      (node (ref "J8") (pin "3") (pinfunction "3_3") (pintype "passive"))
    )
    (net (code "54") (name "/DP6_C2M_P") (class "Default")
      (node (ref "J7") (pin "3") (pinfunction "3_3") (pintype "passive"))
    )
    (net (code "55") (name "/DP6_M2C_N") (class "Default")
      (node (ref "J48") (pin "3") (pinfunction "3_3") (pintype "passive"))
    )
    (net (code "56") (name "/DP6_M2C_P") (class "Default")
      (node (ref "J47") (pin "3") (pinfunction "3_3") (pintype "passive"))
    )
    (net (code "57") (name "/E2") (class "Default")
      (node (ref "J56") (pin "3") (pinfunction "3_3") (pintype "passive"))
    )
    (net (code "58") (name "/E3") (class "Default")
      (node (ref "J44") (pin "3") (pinfunction "3_3") (pintype "passive"))
    )
    (net (code "59") (name "/E6") (class "Default")
      (node (ref "J33") (pin "3") (pinfunction "3_3") (pintype "passive"))
    )
    (net (code "60") (name "/E7") (class "Default")
      (node (ref "J21") (pin "3") (pinfunction "3_3") (pintype "passive"))
    )
    (net (code "61") (name "/E9") (class "Default")
      (node (ref "J54") (pin "3") (pinfunction "3_3") (pintype "passive"))
    )
    (net (code "62") (name "/E10") (class "Default")
      (node (ref "J42") (pin "3") (pinfunction "3_3") (pintype "passive"))
    )
    (net (code "63") (name "/E12") (class "Default")
      (node (ref "J77") (pin "3") (pinfunction "3_3") (pintype "passive"))
    )
    (net (code "64") (name "/E13") (class "Default")
      (node (ref "J65") (pin "3") (pinfunction "3_3") (pintype "passive"))
    )
    (net (code "65") (name "/E15") (class "Default")
      (node (ref "J29") (pin "3") (pinfunction "3_3") (pintype "passive"))
    )
    (net (code "66") (name "/E16") (class "Default")
      (node (ref "J17") (pin "3") (pinfunction "3_3") (pintype "passive"))
    )
    (net (code "67") (name "/E18") (class "Default")
      (node (ref "J40") (pin "3") (pinfunction "3_3") (pintype "passive"))
    )
    (net (code "68") (name "/E19") (class "Default")
      (node (ref "J52") (pin "3") (pinfunction "3_3") (pintype "passive"))
    )
    (net (code "69") (name "/F4") (class "Default")
      (node (ref "J32") (pin "3") (pinfunction "3_3") (pintype "passive"))
    )
    (net (code "70") (name "/F5") (class "Default")
      (node (ref "J20") (pin "3") (pinfunction "3_3") (pintype "passive"))
    )
    (net (code "71") (name "/F7") (class "Default")
      (node (ref "J78") (pin "3") (pinfunction "3_3") (pintype "passive"))
    )
    (net (code "72") (name "/F8") (class "Default")
      (node (ref "J66") (pin "3") (pinfunction "3_3") (pintype "passive"))
    )
    (net (code "73") (name "/F10") (class "Default")
      (node (ref "J30") (pin "3") (pinfunction "3_3") (pintype "passive"))
    )
    (net (code "74") (name "/F11") (class "Default")
      (node (ref "J18") (pin "3") (pinfunction "3_3") (pintype "passive"))
    )
    (net (code "75") (name "/F13") (class "Default")
      (node (ref "J53") (pin "3") (pinfunction "3_3") (pintype "passive"))
    )
    (net (code "76") (name "/F14") (class "Default")
      (node (ref "J41") (pin "3") (pinfunction "3_3") (pintype "passive"))
    )
    (net (code "77") (name "/F16") (class "Default")
      (node (ref "J28") (pin "3") (pinfunction "3_3") (pintype "passive"))
    )
    (net (code "78") (name "/F17") (class "Default")
      (node (ref "J16") (pin "3") (pinfunction "3_3") (pintype "passive"))
    )
    (net (code "79") (name "/F19") (class "Default")
      (node (ref "J64") (pin "3") (pinfunction "3_3") (pintype "passive"))
    )
    (net (code "80") (name "/F20") (class "Default")
      (node (ref "J76") (pin "3") (pinfunction "3_3") (pintype "passive"))
    )
    (net (code "81") (name "/G2") (class "Default")
      (node (ref "J80") (pin "3") (pinfunction "3_3") (pintype "passive"))
    )
    (net (code "82") (name "/G3") (class "Default")
      (node (ref "J68") (pin "3") (pinfunction "3_3") (pintype "passive"))
    )
    (net (code "83") (name "/K22") (class "Default")
      (node (ref "J12") (pin "3") (pinfunction "3_3") (pintype "passive"))
    )
    (net (code "84") (name "/K23") (class "Default")
      (node (ref "J11") (pin "3") (pinfunction "3_3") (pintype "passive"))
    )
    (net (code "85") (name "GND") (class "Default")
      (node (ref "J1") (pin "1") (pinfunction "1_1") (pintype "passive"))
      (node (ref "J1") (pin "2") (pinfunction "2_2") (pintype "passive"))
      (node (ref "J10") (pin "1") (pinfunction "1_1") (pintype "passive"))
      (node (ref "J10") (pin "2") (pinfunction "2_2") (pintype "passive"))
      (node (ref "J11") (pin "1") (pinfunction "1_1") (pintype "passive"))
      (node (ref "J11") (pin "2") (pinfunction "2_2") (pintype "passive"))
      (node (ref "J12") (pin "1") (pinfunction "1_1") (pintype "passive"))
      (node (ref "J12") (pin "2") (pinfunction "2_2") (pintype "passive"))
      (node (ref "J13") (pin "1") (pinfunction "1_1") (pintype "passive"))
      (node (ref "J13") (pin "2") (pinfunction "2_2") (pintype "passive"))
      (node (ref "J14") (pin "1") (pinfunction "1_1") (pintype "passive"))
      (node (ref "J14") (pin "2") (pinfunction "2_2") (pintype "passive"))
      (node (ref "J15") (pin "1") (pinfunction "1_1") (pintype "passive"))
      (node (ref "J15") (pin "2") (pinfunction "2_2") (pintype "passive"))
      (node (ref "J16") (pin "1") (pinfunction "1_1") (pintype "passive"))
      (node (ref "J16") (pin "2") (pinfunction "2_2") (pintype "passive"))
      (node (ref "J17") (pin "1") (pinfunction "1_1") (pintype "passive"))
      (node (ref "J17") (pin "2") (pinfunction "2_2") (pintype "passive"))
      (node (ref "J18") (pin "1") (pinfunction "1_1") (pintype "passive"))
      (node (ref "J18") (pin "2") (pinfunction "2_2") (pintype "passive"))
      (node (ref "J19") (pin "1") (pinfunction "1_1") (pintype "passive"))
      (node (ref "J19") (pin "2") (pinfunction "2_2") (pintype "passive"))
      (node (ref "J2") (pin "1") (pinfunction "1_1") (pintype "passive"))
      (node (ref "J2") (pin "2") (pinfunction "2_2") (pintype "passive"))
      (node (ref "J20") (pin "1") (pinfunction "1_1") (pintype "passive"))
      (node (ref "J20") (pin "2") (pinfunction "2_2") (pintype "passive"))
      (node (ref "J21") (pin "1") (pinfunction "1_1") (pintype "passive"))
      (node (ref "J21") (pin "2") (pinfunction "2_2") (pintype "passive"))
      (node (ref "J22") (pin "1") (pinfunction "1_1") (pintype "passive"))
      (node (ref "J22") (pin "2") (pinfunction "2_2") (pintype "passive"))
      (node (ref "J23") (pin "1") (pinfunction "1_1") (pintype "passive"))
      (node (ref "J23") (pin "2") (pinfunction "2_2") (pintype "passive"))
      (node (ref "J24") (pin "1") (pinfunction "1_1") (pintype "passive"))
      (node (ref "J24") (pin "2") (pinfunction "2_2") (pintype "passive"))
      (node (ref "J25") (pin "1") (pinfunction "1_1") (pintype "passive"))
      (node (ref "J25") (pin "2") (pinfunction "2_2") (pintype "passive"))
      (node (ref "J26") (pin "1") (pinfunction "1_1") (pintype "passive"))
      (node (ref "J26") (pin "2") (pinfunction "2_2") (pintype "passive"))
      (node (ref "J27") (pin "1") (pinfunction "1_1") (pintype "passive"))
      (node (ref "J27") (pin "2") (pinfunction "2_2") (pintype "passive"))
      (node (ref "J28") (pin "1") (pinfunction "1_1") (pintype "passive"))
      (node (ref "J28") (pin "2") (pinfunction "2_2") (pintype "passive"))
      (node (ref "J29") (pin "1") (pinfunction "1_1") (pintype "passive"))
      (node (ref "J29") (pin "2") (pinfunction "2_2") (pintype "passive"))
      (node (ref "J3") (pin "1") (pinfunction "1_1") (pintype "passive"))
      (node (ref "J3") (pin "2") (pinfunction "2_2") (pintype "passive"))
      (node (ref "J30") (pin "1") (pinfunction "1_1") (pintype "passive"))
      (node (ref "J30") (pin "2") (pinfunction "2_2") (pintype "passive"))
      (node (ref "J31") (pin "1") (pinfunction "1_1") (pintype "passive"))
      (node (ref "J31") (pin "2") (pinfunction "2_2") (pintype "passive"))
      (node (ref "J32") (pin "1") (pinfunction "1_1") (pintype "passive"))
      (node (ref "J32") (pin "2") (pinfunction "2_2") (pintype "passive"))
      (node (ref "J33") (pin "1") (pinfunction "1_1") (pintype "passive"))
      (node (ref "J33") (pin "2") (pinfunction "2_2") (pintype "passive"))
      (node (ref "J34") (pin "1") (pinfunction "1_1") (pintype "passive"))
      (node (ref "J34") (pin "2") (pinfunction "2_2") (pintype "passive"))
      (node (ref "J35") (pin "1") (pinfunction "1_1") (pintype "passive"))
      (node (ref "J35") (pin "2") (pinfunction "2_2") (pintype "passive"))
      (node (ref "J36") (pin "1") (pinfunction "1_1") (pintype "passive"))
      (node (ref "J36") (pin "2") (pinfunction "2_2") (pintype "passive"))
      (node (ref "J37") (pin "1") (pinfunction "1_1") (pintype "passive"))
      (node (ref "J37") (pin "2") (pinfunction "2_2") (pintype "passive"))
      (node (ref "J38") (pin "1") (pinfunction "1_1") (pintype "passive"))
      (node (ref "J38") (pin "2") (pinfunction "2_2") (pintype "passive"))
      (node (ref "J39") (pin "1") (pinfunction "1_1") (pintype "passive"))
      (node (ref "J39") (pin "2") (pinfunction "2_2") (pintype "passive"))
      (node (ref "J4") (pin "1") (pinfunction "1_1") (pintype "passive"))
      (node (ref "J4") (pin "2") (pinfunction "2_2") (pintype "passive"))
      (node (ref "J40") (pin "1") (pinfunction "1_1") (pintype "passive"))
      (node (ref "J40") (pin "2") (pinfunction "2_2") (pintype "passive"))
      (node (ref "J41") (pin "1") (pinfunction "1_1") (pintype "passive"))
      (node (ref "J41") (pin "2") (pinfunction "2_2") (pintype "passive"))
      (node (ref "J42") (pin "1") (pinfunction "1_1") (pintype "passive"))
      (node (ref "J42") (pin "2") (pinfunction "2_2") (pintype "passive"))
      (node (ref "J43") (pin "1") (pinfunction "1_1") (pintype "passive"))
      (node (ref "J43") (pin "2") (pinfunction "2_2") (pintype "passive"))
      (node (ref "J44") (pin "1") (pinfunction "1_1") (pintype "passive"))
      (node (ref "J44") (pin "2") (pinfunction "2_2") (pintype "passive"))
      (node (ref "J45") (pin "1") (pinfunction "1_1") (pintype "passive"))
      (node (ref "J45") (pin "2") (pinfunction "2_2") (pintype "passive"))
      (node (ref "J46") (pin "1") (pinfunction "1_1") (pintype "passive"))
      (node (ref "J46") (pin "2") (pinfunction "2_2") (pintype "passive"))
      (node (ref "J47") (pin "1") (pinfunction "1_1") (pintype "passive"))
      (node (ref "J47") (pin "2") (pinfunction "2_2") (pintype "passive"))
      (node (ref "J48") (pin "1") (pinfunction "1_1") (pintype "passive"))
      (node (ref "J48") (pin "2") (pinfunction "2_2") (pintype "passive"))
      (node (ref "J49") (pin "1") (pinfunction "1_1") (pintype "passive"))
      (node (ref "J49") (pin "2") (pinfunction "2_2") (pintype "passive"))
      (node (ref "J5") (pin "1") (pinfunction "1_1") (pintype "passive"))
      (node (ref "J5") (pin "2") (pinfunction "2_2") (pintype "passive"))
      (node (ref "J50") (pin "1") (pinfunction "1_1") (pintype "passive"))
      (node (ref "J50") (pin "2") (pinfunction "2_2") (pintype "passive"))
      (node (ref "J51") (pin "1") (pinfunction "1_1") (pintype "passive"))
      (node (ref "J51") (pin "2") (pinfunction "2_2") (pintype "passive"))
      (node (ref "J52") (pin "1") (pinfunction "1_1") (pintype "passive"))
      (node (ref "J52") (pin "2") (pinfunction "2_2") (pintype "passive"))
      (node (ref "J53") (pin "1") (pinfunction "1_1") (pintype "passive"))
      (node (ref "J53") (pin "2") (pinfunction "2_2") (pintype "passive"))
      (node (ref "J54") (pin "1") (pinfunction "1_1") (pintype "passive"))
      (node (ref "J54") (pin "2") (pinfunction "2_2") (pintype "passive"))
      (node (ref "J55") (pin "1") (pinfunction "1_1") (pintype "passive"))
      (node (ref "J55") (pin "2") (pinfunction "2_2") (pintype "passive"))
      (node (ref "J56") (pin "1") (pinfunction "1_1") (pintype "passive"))
      (node (ref "J56") (pin "2") (pinfunction "2_2") (pintype "passive"))
      (node (ref "J57") (pin "1") (pinfunction "1_1") (pintype "passive"))
      (node (ref "J57") (pin "2") (pinfunction "2_2") (pintype "passive"))
      (node (ref "J58") (pin "1") (pinfunction "1_1") (pintype "passive"))
      (node (ref "J58") (pin "2") (pinfunction "2_2") (pintype "passive"))
      (node (ref "J59") (pin "1") (pinfunction "1_1") (pintype "passive"))
      (node (ref "J59") (pin "2") (pinfunction "2_2") (pintype "passive"))
      (node (ref "J6") (pin "1") (pinfunction "1_1") (pintype "passive"))
      (node (ref "J6") (pin "2") (pinfunction "2_2") (pintype "passive"))
      (node (ref "J60") (pin "1") (pinfunction "1_1") (pintype "passive"))
      (node (ref "J60") (pin "2") (pinfunction "2_2") (pintype "passive"))
      (node (ref "J61") (pin "1") (pinfunction "1_1") (pintype "passive"))
      (node (ref "J61") (pin "2") (pinfunction "2_2") (pintype "passive"))
      (node (ref "J62") (pin "1") (pinfunction "1_1") (pintype "passive"))
      (node (ref "J62") (pin "2") (pinfunction "2_2") (pintype "passive"))
      (node (ref "J63") (pin "1") (pinfunction "1_1") (pintype "passive"))
      (node (ref "J63") (pin "2") (pinfunction "2_2") (pintype "passive"))
      (node (ref "J64") (pin "1") (pinfunction "1_1") (pintype "passive"))
      (node (ref "J64") (pin "2") (pinfunction "2_2") (pintype "passive"))
      (node (ref "J65") (pin "1") (pinfunction "1_1") (pintype "passive"))
      (node (ref "J65") (pin "2") (pinfunction "2_2") (pintype "passive"))
      (node (ref "J66") (pin "1") (pinfunction "1_1") (pintype "passive"))
      (node (ref "J66") (pin "2") (pinfunction "2_2") (pintype "passive"))
      (node (ref "J67") (pin "1") (pinfunction "1_1") (pintype "passive"))
      (node (ref "J67") (pin "2") (pinfunction "2_2") (pintype "passive"))
      (node (ref "J68") (pin "1") (pinfunction "1_1") (pintype "passive"))
      (node (ref "J68") (pin "2") (pinfunction "2_2") (pintype "passive"))
      (node (ref "J69") (pin "1") (pinfunction "1_1") (pintype "passive"))
      (node (ref "J69") (pin "2") (pinfunction "2_2") (pintype "passive"))
      (node (ref "J7") (pin "1") (pinfunction "1_1") (pintype "passive"))
      (node (ref "J7") (pin "2") (pinfunction "2_2") (pintype "passive"))
      (node (ref "J70") (pin "1") (pinfunction "1_1") (pintype "passive"))
      (node (ref "J70") (pin "2") (pinfunction "2_2") (pintype "passive"))
      (node (ref "J71") (pin "1") (pinfunction "1_1") (pintype "passive"))
      (node (ref "J71") (pin "2") (pinfunction "2_2") (pintype "passive"))
      (node (ref "J72") (pin "1") (pinfunction "1_1") (pintype "passive"))
      (node (ref "J72") (pin "2") (pinfunction "2_2") (pintype "passive"))
      (node (ref "J73") (pin "1") (pinfunction "1_1") (pintype "passive"))
      (node (ref "J73") (pin "2") (pinfunction "2_2") (pintype "passive"))
      (node (ref "J74") (pin "1") (pinfunction "1_1") (pintype "passive"))
      (node (ref "J74") (pin "2") (pinfunction "2_2") (pintype "passive"))
      (node (ref "J75") (pin "1") (pinfunction "1_1") (pintype "passive"))
      (node (ref "J75") (pin "2") (pinfunction "2_2") (pintype "passive"))
      (node (ref "J76") (pin "1") (pinfunction "1_1") (pintype "passive"))
      (node (ref "J76") (pin "2") (pinfunction "2_2") (pintype "passive"))
      (node (ref "J77") (pin "1") (pinfunction "1_1") (pintype "passive"))
      (node (ref "J77") (pin "2") (pinfunction "2_2") (pintype "passive"))
      (node (ref "J78") (pin "1") (pinfunction "1_1") (pintype "passive"))
      (node (ref "J78") (pin "2") (pinfunction "2_2") (pintype "passive"))
      (node (ref "J79") (pin "1") (pinfunction "1_1") (pintype "passive"))
      (node (ref "J79") (pin "2") (pinfunction "2_2") (pintype "passive"))
      (node (ref "J8") (pin "1") (pinfunction "1_1") (pintype "passive"))
      (node (ref "J8") (pin "2") (pinfunction "2_2") (pintype "passive"))
      (node (ref "J80") (pin "1") (pinfunction "1_1") (pintype "passive"))
      (node (ref "J80") (pin "2") (pinfunction "2_2") (pintype "passive"))
      (node (ref "J81") (pin "1") (pinfunction "1_1") (pintype "passive"))
      (node (ref "J81") (pin "2") (pinfunction "2_2") (pintype "passive"))
      (node (ref "J82") (pin "1") (pinfunction "1_1") (pintype "passive"))
      (node (ref "J82") (pin "2") (pinfunction "2_2") (pintype "passive"))
      (node (ref "J83") (pin "1") (pinfunction "1_1") (pintype "passive"))
      (node (ref "J83") (pin "2") (pinfunction "2_2") (pintype "passive"))
      (node (ref "J84") (pin "1") (pinfunction "1_1") (pintype "passive"))
      (node (ref "J84") (pin "2") (pinfunction "2_2") (pintype "passive"))
      (node (ref "J9") (pin "1") (pinfunction "1_1") (pintype "passive"))
      (node (ref "J9") (pin "2") (pinfunction "2_2") (pintype "passive"))
    )
  )
)
